# esp.net
KiCad netlist of a schematic drawn in EAGLE
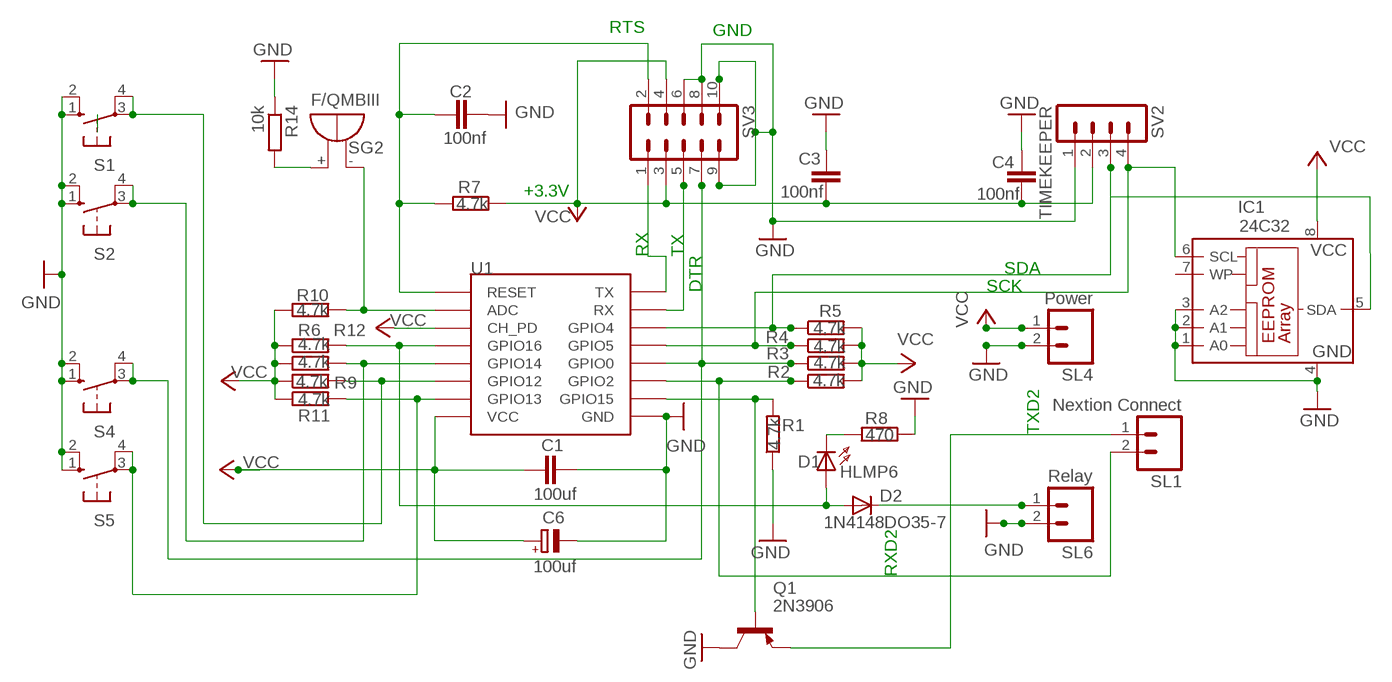
[diagram p0: schematic, sheet 1]

(export (version "E")
  (design (tool "Eeschema 10.0.6"))
  (components
    (comp (ref "C1")
      (value "100uf")
      (footprint "eagle-import:C0805")
      (libsource (lib "eagle-import") (part "C"))
    )
    (comp (ref "C2")
      (value "100nf")
      (footprint "eagle-import:C0805")
      (libsource (lib "eagle-import") (part "C"))
    )
    (comp (ref "C3")
      (value "100nf")
      (footprint "eagle-import:C0805")
      (libsource (lib "eagle-import") (part "C"))
    )
    (comp (ref "C4")
      (value "100nf")
      (footprint "eagle-import:C0805")
      (libsource (lib "eagle-import") (part "C"))
    )
    (comp (ref "C6")
      (value "100uf")
      (footprint "eagle-import:E5-10,5")
      (libsource (lib "eagle-import") (part "CPOL-EUE5-10.5"))
    )
    (comp (ref "D1")
      (value "HLMP6")
      (footprint "eagle-import:HLMP6")
      (fields (field (name "MF") "AGILENT TECHNOLOGIES") (field (name "MPN") "HLMP-6500"))
      (libsource (lib "eagle-import") (part "HLMP6"))
    )
    (comp (ref "D2")
      (value "1N4148DO35-7")
      (footprint "eagle-import:DO35-7")
      (libsource (lib "eagle-import") (part "1N4148DO35-7"))
    )
    (comp (ref "IC1")
      (value "24C32")
      (footprint "eagle-import:SO-08")
      (libsource (lib "eagle-import") (part "24CSN04C"))
    )
    (comp (ref "Q1")
      (value "2N3906")
      (footprint "eagle-import:TO92")
      (libsource (lib "eagle-import") (part "2N3906"))
    )
    (comp (ref "R1")
      (value "4.7k")
      (footprint "eagle-import:R0805")
      (libsource (lib "eagle-import") (part "R"))
    )
    (comp (ref "R2")
      (value "4.7k")
      (footprint "eagle-import:R0805")
      (libsource (lib "eagle-import") (part "R"))
    )
    (comp (ref "R3")
      (value "4.7k")
      (footprint "eagle-import:R0805")
      (libsource (lib "eagle-import") (part "R"))
    )
    (comp (ref "R4")
      (value "4.7k")
      (footprint "eagle-import:R0805")
      (libsource (lib "eagle-import") (part "R"))
    )
    (comp (ref "R5")
      (value "4.7k")
      (footprint "eagle-import:R0805")
      (libsource (lib "eagle-import") (part "R"))
    )
    (comp (ref "R6")
      (value "4.7k")
      (footprint "eagle-import:R0805")
      (libsource (lib "eagle-import") (part "R"))
    )
    (comp (ref "R7")
      (value "4.7k")
      (footprint "eagle-import:R0805")
      (libsource (lib "eagle-import") (part "R"))
    )
    (comp (ref "R8")
      (value "470")
      (footprint "eagle-import:R0805")
      (libsource (lib "eagle-import") (part "R"))
    )
    (comp (ref "R9")
      (value "4.7k")
      (footprint "eagle-import:R0805")
      (libsource (lib "eagle-import") (part "R"))
    )
    (comp (ref "R10")
      (value "4.7k")
      (footprint "eagle-import:R0805")
      (libsource (lib "eagle-import") (part "R"))
    )
    (comp (ref "R11")
      (value "4.7k")
      (footprint "eagle-import:R0805")
      (libsource (lib "eagle-import") (part "R"))
    )
    (comp (ref "R12")
      (value "4.7k")
      (footprint "eagle-import:R0805")
      (libsource (lib "eagle-import") (part "R"))
    )
    (comp (ref "R14")
      (value "10k")
      (footprint "eagle-import:R0805")
      (libsource (lib "eagle-import") (part "R"))
    )
    (comp (ref "S1")
      (value "10-XX")
      (footprint "eagle-import:B3F-10XX")
      (fields (field (name "MPN") "B3F-1000"))
      (libsource (lib "eagle-import") (part "10-XX"))
    )
    (comp (ref "S2")
      (value "10-XX")
      (footprint "eagle-import:B3F-10XX")
      (fields (field (name "MPN") "B3F-1000"))
      (libsource (lib "eagle-import") (part "10-XX"))
    )
    (comp (ref "S4")
      (value "10-XX")
      (footprint "eagle-import:B3F-10XX")
      (fields (field (name "MPN") "B3F-1000"))
      (libsource (lib "eagle-import") (part "10-XX"))
    )
    (comp (ref "S5")
      (value "10-XX")
      (footprint "eagle-import:B3F-10XX")
      (fields (field (name "MPN") "B3F-1000"))
      (libsource (lib "eagle-import") (part "10-XX"))
    )
    (comp (ref "SG2")
      (value "F/QMBIII")
      (footprint "eagle-import:F_QMBIII")
      (libsource (lib "eagle-import") (part "F/QMBIII"))
    )
    (comp (ref "SL1")
      (value "Nextion Connect")
      (footprint "eagle-import:02P")
      (libsource (lib "eagle-import") (part "M02"))
    )
    (comp (ref "SL4")
      (value "Power")
      (footprint "eagle-import:02P")
      (libsource (lib "eagle-import") (part "M02"))
    )
    (comp (ref "SL6")
      (value "Relay")
      (footprint "eagle-import:02P")
      (libsource (lib "eagle-import") (part "M02"))
    )
    (comp (ref "SV2")
      (value "TIMEKEEPER")
      (footprint "eagle-import:MA04-1")
      (libsource (lib "eagle-import") (part "MA04-1"))
    )
    (comp (ref "SV3")
      (value "MA05-2")
      (footprint "eagle-import:MA05-2")
      (libsource (lib "eagle-import") (part "MA05-2"))
    )
    (comp (ref "U1")
      (value "ESP12SMD")
      (footprint "eagle-import:ESP12-SMD")
      (libsource (lib "eagle-import") (part "ESP12SMD"))
    )
  )
  (nets
    (net (code "1") (name "GND") (class "Default")
      (node (ref "C1") (pin "1") (pinfunction "1_1") (pintype "passive"))
      (node (ref "C2") (pin "1") (pinfunction "1_1") (pintype "passive"))
      (node (ref "C3") (pin "2") (pinfunction "2_2") (pintype "passive"))
      (node (ref "C4") (pin "2") (pinfunction "2_2") (pintype "passive"))
      (node (ref "C6") (pin "-") (pinfunction "-_-") (pintype "passive"))
      (node (ref "IC1") (pin "1") (pinfunction "A0_1") (pintype "input"))
      (node (ref "IC1") (pin "2") (pinfunction "A1_2") (pintype "input"))
      (node (ref "IC1") (pin "3") (pinfunction "A2_3") (pintype "input"))
      (node (ref "IC1") (pin "4") (pinfunction "GND_4") (pintype "power_in"))
      (node (ref "Q1") (pin "1") (pinfunction "C_1") (pintype "passive"))
      (node (ref "R1") (pin "1") (pinfunction "1_1") (pintype "passive"))
      (node (ref "R14") (pin "1") (pinfunction "1_1") (pintype "passive"))
      (node (ref "R8") (pin "1") (pinfunction "1_1") (pintype "passive"))
      (node (ref "S1") (pin "1") (pinfunction "S_1") (pintype "passive"))
      (node (ref "S1") (pin "2") (pinfunction "S1_2") (pintype "passive"))
      (node (ref "S2") (pin "1") (pinfunction "S_1") (pintype "passive"))
      (node (ref "S2") (pin "2") (pinfunction "S1_2") (pintype "passive"))
      (node (ref "S4") (pin "1") (pinfunction "S_1") (pintype "passive"))
      (node (ref "S4") (pin "2") (pinfunction "S1_2") (pintype "passive"))
      (node (ref "S5") (pin "1") (pinfunction "S_1") (pintype "passive"))
      (node (ref "S5") (pin "2") (pinfunction "S1_2") (pintype "passive"))
      (node (ref "SL4") (pin "2") (pinfunction "2_2") (pintype "passive"))
      (node (ref "SL6") (pin "2") (pinfunction "2_2") (pintype "passive"))
      (node (ref "SV2") (pin "1") (pinfunction "1_1") (pintype "passive"))
      (node (ref "SV3") (pin "10") (pinfunction "10_10") (pintype "passive"))
      (node (ref "SV3") (pin "6") (pinfunction "6_6") (pintype "passive"))
      (node (ref "SV3") (pin "8") (pinfunction "8_8") (pintype "passive"))
      (node (ref "SV3") (pin "9") (pinfunction "9_9") (pintype "passive"))
      (node (ref "U1") (pin "GND") (pinfunction "GND_GND") (pintype "bidirectional"))
    )
    (net (code "2") (name "Net-(C2-Pad2)") (class "Default")
      (node (ref "C2") (pin "2") (pinfunction "2_2") (pintype "passive"))
      (node (ref "R7") (pin "2") (pinfunction "2_2") (pintype "passive"))
      (node (ref "SV3") (pin "2") (pinfunction "2_2") (pintype "passive"))
      (node (ref "U1") (pin "RESET") (pinfunction "RESET_RESET") (pintype "bidirectional"))
    )
    (net (code "3") (name "Net-(D1-PadA)") (class "Default")
      (node (ref "D1") (pin "A") (pinfunction "A_A") (pintype "passive"))
      (node (ref "D2") (pin "A") (pinfunction "A_A") (pintype "passive"))
      (node (ref "R6") (pin "2") (pinfunction "2_2") (pintype "passive"))
      (node (ref "U1") (pin "GPIO16") (pinfunction "GPIO16_GPIO16") (pintype "bidirectional"))
    )
    (net (code "4") (name "Net-(D1-PadK)") (class "Default")
      (node (ref "D1") (pin "K") (pinfunction "K_K") (pintype "passive"))
      (node (ref "R8") (pin "2") (pinfunction "2_2") (pintype "passive"))
    )
    (net (code "5") (name "Net-(D2-PadC)") (class "Default")
      (node (ref "D2") (pin "C") (pinfunction "C_C") (pintype "passive"))
      (node (ref "SL6") (pin "1") (pinfunction "1_1") (pintype "passive"))
    )
    (net (code "6") (name "Net-(IC1-SCL)") (class "Default")
      (node (ref "IC1") (pin "6") (pinfunction "SCL_6") (pintype "input"))
      (node (ref "R4") (pin "1") (pinfunction "1_1") (pintype "passive"))
      (node (ref "SV2") (pin "4") (pinfunction "4_4") (pintype "passive"))
      (node (ref "U1") (pin "GPIO5") (pinfunction "GPIO5_GPIO5") (pintype "bidirectional"))
    )
    (net (code "7") (name "Net-(IC1-SDA)") (class "Default")
      (node (ref "IC1") (pin "5") (pinfunction "SDA_5") (pintype "bidirectional"))
      (node (ref "R5") (pin "1") (pinfunction "1_1") (pintype "passive"))
      (node (ref "SV2") (pin "3") (pinfunction "3_3") (pintype "passive"))
      (node (ref "U1") (pin "GPIO4") (pinfunction "GPIO4_GPIO4") (pintype "bidirectional"))
    )
    (net (code "8") (name "Net-(Q1-B)") (class "Default")
      (node (ref "Q1") (pin "2") (pinfunction "B_2") (pintype "passive"))
      (node (ref "R1") (pin "2") (pinfunction "2_2") (pintype "passive"))
      (node (ref "U1") (pin "GPIO15") (pinfunction "GPIO15_GPIO15") (pintype "bidirectional"))
    )
    (net (code "9") (name "Net-(Q1-E)") (class "Default")
      (node (ref "Q1") (pin "3") (pinfunction "E_3") (pintype "passive"))
      (node (ref "SL1") (pin "1") (pinfunction "1_1") (pintype "passive"))
    )
    (net (code "10") (name "Net-(R2-Pad1)") (class "Default")
      (node (ref "R2") (pin "1") (pinfunction "1_1") (pintype "passive"))
      (node (ref "SL1") (pin "2") (pinfunction "2_2") (pintype "passive"))
      (node (ref "U1") (pin "GPIO2") (pinfunction "GPIO2_GPIO2") (pintype "bidirectional"))
    )
    (net (code "11") (name "Net-(S1-P)") (class "Default")
      (node (ref "R9") (pin "2") (pinfunction "2_2") (pintype "passive"))
      (node (ref "S1") (pin "3") (pinfunction "P_3") (pintype "passive"))
      (node (ref "S1") (pin "4") (pinfunction "P1_4") (pintype "passive"))
      (node (ref "U1") (pin "GPIO12") (pinfunction "GPIO12_GPIO12") (pintype "bidirectional"))
    )
    (net (code "12") (name "Net-(S2-P)") (class "Default")
      (node (ref "R12") (pin "2") (pinfunction "2_2") (pintype "passive"))
      (node (ref "S2") (pin "3") (pinfunction "P_3") (pintype "passive"))
      (node (ref "S2") (pin "4") (pinfunction "P1_4") (pintype "passive"))
      (node (ref "U1") (pin "GPIO14") (pinfunction "GPIO14_GPIO14") (pintype "bidirectional"))
    )
    (net (code "13") (name "Net-(S4-P)") (class "Default")
      (node (ref "R3") (pin "1") (pinfunction "1_1") (pintype "passive"))
      (node (ref "S4") (pin "3") (pinfunction "P_3") (pintype "passive"))
      (node (ref "S4") (pin "4") (pinfunction "P1_4") (pintype "passive"))
      (node (ref "SV3") (pin "7") (pinfunction "7_7") (pintype "passive"))
      (node (ref "U1") (pin "GPIO0") (pinfunction "GPIO0_GPIO0") (pintype "bidirectional"))
    )
    (net (code "14") (name "Net-(S5-P)") (class "Default")
      (node (ref "R11") (pin "2") (pinfunction "2_2") (pintype "passive"))
      (node (ref "S5") (pin "3") (pinfunction "P_3") (pintype "passive"))
      (node (ref "S5") (pin "4") (pinfunction "P1_4") (pintype "passive"))
      (node (ref "U1") (pin "GPIO13") (pinfunction "GPIO13_GPIO13") (pintype "bidirectional"))
    )
    (net (code "15") (name "Net-(SG2-+)") (class "Default")
      (node (ref "R10") (pin "2") (pinfunction "2_2") (pintype "passive"))
      (node (ref "SG2") (pin "-") (pinfunction "+_-") (pintype "passive"))
      (node (ref "U1") (pin "ADC") (pinfunction "ADC_ADC") (pintype "bidirectional"))
    )
    (net (code "16") (name "Net-(SG2--)") (class "Default")
      (node (ref "R14") (pin "2") (pinfunction "2_2") (pintype "passive"))
      (node (ref "SG2") (pin "+") (pinfunction "-_+") (pintype "passive"))
    )
    (net (code "17") (name "Net-(U1-RX)") (class "Default")
      (node (ref "SV3") (pin "5") (pinfunction "5_5") (pintype "passive"))
      (node (ref "U1") (pin "RXD0") (pinfunction "RX_RXD0") (pintype "bidirectional"))
    )
    (net (code "18") (name "Net-(U1-TX)") (class "Default")
      (node (ref "SV3") (pin "1") (pinfunction "1_1") (pintype "passive"))
      (node (ref "U1") (pin "TXD0") (pinfunction "TX_TXD0") (pintype "bidirectional"))
    )
    (net (code "19") (name "VCC") (class "Default")
      (node (ref "C1") (pin "2") (pinfunction "2_2") (pintype "passive"))
      (node (ref "C3") (pin "1") (pinfunction "1_1") (pintype "passive"))
      (node (ref "C4") (pin "1") (pinfunction "1_1") (pintype "passive"))
      (node (ref "C6") (pin "+") (pinfunction "+_+") (pintype "passive"))
      (node (ref "IC1") (pin "8") (pinfunction "VCC_8") (pintype "power_in"))
      (node (ref "R10") (pin "1") (pinfunction "1_1") (pintype "passive"))
      (node (ref "R11") (pin "1") (pinfunction "1_1") (pintype "passive"))
      (node (ref "R12") (pin "1") (pinfunction "1_1") (pintype "passive"))
      (node (ref "R2") (pin "2") (pinfunction "2_2") (pintype "passive"))
      (node (ref "R3") (pin "2") (pinfunction "2_2") (pintype "passive"))
      (node (ref "R4") (pin "2") (pinfunction "2_2") (pintype "passive"))
      (node (ref "R5") (pin "2") (pinfunction "2_2") (pintype "passive"))
      (node (ref "R6") (pin "1") (pinfunction "1_1") (pintype "passive"))
      (node (ref "R7") (pin "1") (pinfunction "1_1") (pintype "passive"))
      (node (ref "R9") (pin "1") (pinfunction "1_1") (pintype "passive"))
      (node (ref "SL4") (pin "1") (pinfunction "1_1") (pintype "passive"))
      (node (ref "SV2") (pin "2") (pinfunction "2_2") (pintype "passive"))
      (node (ref "SV3") (pin "3") (pinfunction "3_3") (pintype "passive"))
      (node (ref "SV3") (pin "4") (pinfunction "4_4") (pintype "passive"))
      (node (ref "U1") (pin "CH_PD") (pinfunction "CH_PD_CH_PD") (pintype "bidirectional"))
      (node (ref "U1") (pin "VCC") (pinfunction "VCC_VCC") (pintype "bidirectional"))
    )
    (net (code "20") (name "unconnected-(IC1-WP-Pad7)") (class "Default")
      (node (ref "IC1") (pin "7") (pinfunction "WP_7") (pintype "input"))
    )
  )
)
